# nes_controller_v1_0_v7.net
KiCad netlist of a schematic drawn in EAGLE
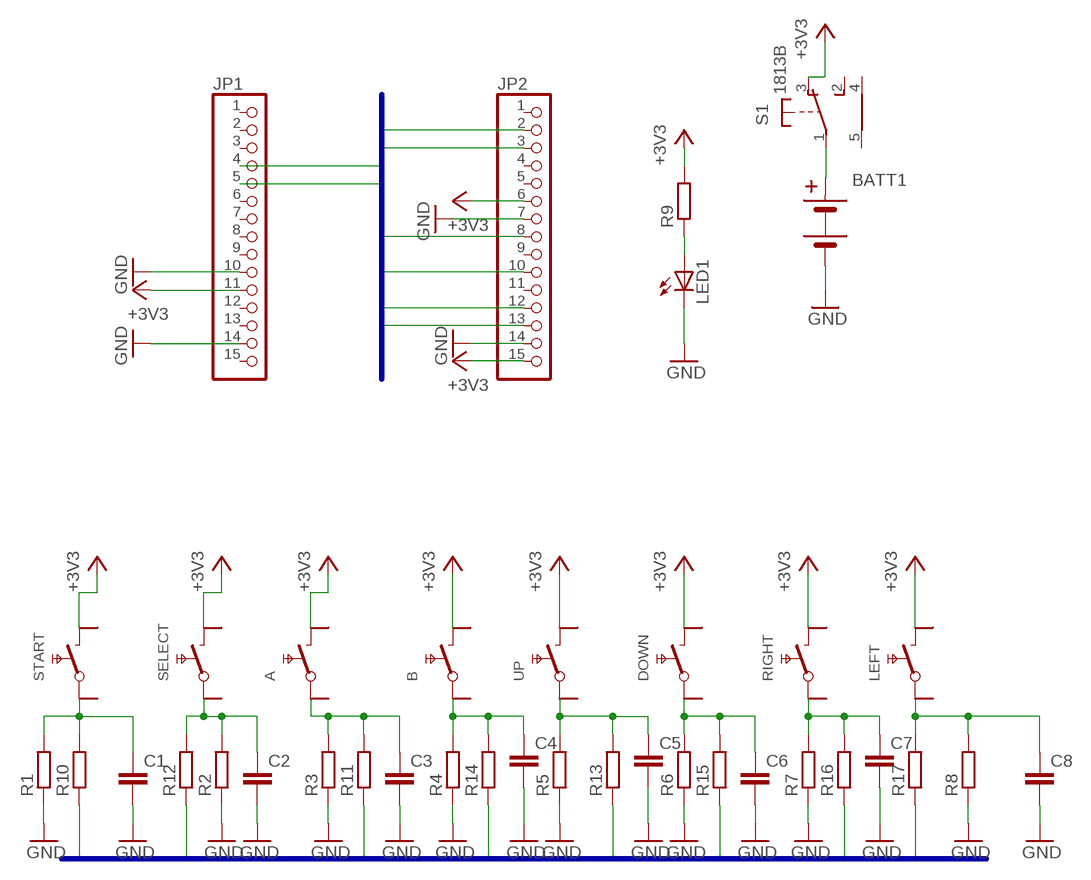
[diagram p0: schematic, sheet 1]

(export (version "E")
  (design (tool "Eeschema 10.0.6"))
  (components
    (comp (ref "A")
      (value "SMDTAST")
      (footprint "eagle-import:SMDTAST")
      (libsource (lib "eagle-import") (part "SMDTAST"))
    )
    (comp (ref "B")
      (value "SMDTAST")
      (footprint "eagle-import:SMDTAST")
      (libsource (lib "eagle-import") (part "SMDTAST"))
    )
    (comp (ref "BATT1")
      (value "BATTERIEHALTER_2X_AAA")
      (footprint "eagle-import:BATTERIEHALTER")
      (libsource (lib "eagle-import") (part "BATTERIEHALTER_2X_AAA"))
    )
    (comp (ref "C1")
      (value "C-EUC0805K")
      (footprint "eagle-import:C0805K")
      (libsource (lib "eagle-import") (part "C-EUC0805K"))
    )
    (comp (ref "C2")
      (value "C-EUC0805K")
      (footprint "eagle-import:C0805K")
      (libsource (lib "eagle-import") (part "C-EUC0805K"))
    )
    (comp (ref "C3")
      (value "C-EUC0805K")
      (footprint "eagle-import:C0805K")
      (libsource (lib "eagle-import") (part "C-EUC0805K"))
    )
    (comp (ref "C4")
      (value "C-EUC0805K")
      (footprint "eagle-import:C0805K")
      (libsource (lib "eagle-import") (part "C-EUC0805K"))
    )
    (comp (ref "C5")
      (value "C-EUC0805K")
      (footprint "eagle-import:C0805K")
      (libsource (lib "eagle-import") (part "C-EUC0805K"))
    )
    (comp (ref "C6")
      (value "C-EUC0805K")
      (footprint "eagle-import:C0805K")
      (libsource (lib "eagle-import") (part "C-EUC0805K"))
    )
    (comp (ref "C7")
      (value "C-EUC0805K")
      (footprint "eagle-import:C0805K")
      (libsource (lib "eagle-import") (part "C-EUC0805K"))
    )
    (comp (ref "C8")
      (value "C-EUC0805K")
      (footprint "eagle-import:C0805K")
      (libsource (lib "eagle-import") (part "C-EUC0805K"))
    )
    (comp (ref "DOWN")
      (value "SMDTAST")
      (footprint "eagle-import:SMDTAST")
      (libsource (lib "eagle-import") (part "SMDTAST"))
    )
    (comp (ref "JP1")
      (value "PINHD-1X15")
      (footprint "eagle-import:1X15")
      (libsource (lib "eagle-import") (part "PINHD-1X15"))
    )
    (comp (ref "JP2")
      (value "PINHD-1X15")
      (footprint "eagle-import:1X15")
      (libsource (lib "eagle-import") (part "PINHD-1X15"))
    )
    (comp (ref "LED1")
      (value "LED3MM")
      (footprint "eagle-import:LED3MM")
      (libsource (lib "eagle-import") (part "LED3MM"))
    )
    (comp (ref "LEFT")
      (value "SMDTAST")
      (footprint "eagle-import:SMDTAST")
      (libsource (lib "eagle-import") (part "SMDTAST"))
    )
    (comp (ref "R1")
      (value "R-EU_MELF0207R")
      (footprint "eagle-import:MINI_MELF-0207R")
      (libsource (lib "eagle-import") (part "R-EU_MELF0207R"))
    )
    (comp (ref "R2")
      (value "R-EU_MELF0207R")
      (footprint "eagle-import:MINI_MELF-0207R")
      (libsource (lib "eagle-import") (part "R-EU_MELF0207R"))
    )
    (comp (ref "R3")
      (value "R-EU_MELF0207R")
      (footprint "eagle-import:MINI_MELF-0207R")
      (libsource (lib "eagle-import") (part "R-EU_MELF0207R"))
    )
    (comp (ref "R4")
      (value "R-EU_MELF0207R")
      (footprint "eagle-import:MINI_MELF-0207R")
      (libsource (lib "eagle-import") (part "R-EU_MELF0207R"))
    )
    (comp (ref "R5")
      (value "R-EU_MELF0207R")
      (footprint "eagle-import:MINI_MELF-0207R")
      (libsource (lib "eagle-import") (part "R-EU_MELF0207R"))
    )
    (comp (ref "R6")
      (value "R-EU_MELF0207R")
      (footprint "eagle-import:MINI_MELF-0207R")
      (libsource (lib "eagle-import") (part "R-EU_MELF0207R"))
    )
    (comp (ref "R7")
      (value "R-EU_MELF0207R")
      (footprint "eagle-import:MINI_MELF-0207R")
      (libsource (lib "eagle-import") (part "R-EU_MELF0207R"))
    )
    (comp (ref "R8")
      (value "R-EU_MELF0207R")
      (footprint "eagle-import:MINI_MELF-0207R")
      (libsource (lib "eagle-import") (part "R-EU_MELF0207R"))
    )
    (comp (ref "R9")
      (value "R-EU_MELF0207R")
      (footprint "eagle-import:MINI_MELF-0207R")
      (libsource (lib "eagle-import") (part "R-EU_MELF0207R"))
    )
    (comp (ref "R10")
      (value "R-EU_MELF0207R")
      (footprint "eagle-import:MINI_MELF-0207R")
      (libsource (lib "eagle-import") (part "R-EU_MELF0207R"))
    )
    (comp (ref "R11")
      (value "R-EU_MELF0207R")
      (footprint "eagle-import:MINI_MELF-0207R")
      (libsource (lib "eagle-import") (part "R-EU_MELF0207R"))
    )
    (comp (ref "R12")
      (value "R-EU_MELF0207R")
      (footprint "eagle-import:MINI_MELF-0207R")
      (libsource (lib "eagle-import") (part "R-EU_MELF0207R"))
    )
    (comp (ref "R13")
      (value "R-EU_MELF0207R")
      (footprint "eagle-import:MINI_MELF-0207R")
      (libsource (lib "eagle-import") (part "R-EU_MELF0207R"))
    )
    (comp (ref "R14")
      (value "R-EU_MELF0207R")
      (footprint "eagle-import:MINI_MELF-0207R")
      (libsource (lib "eagle-import") (part "R-EU_MELF0207R"))
    )
    (comp (ref "R15")
      (value "R-EU_MELF0207R")
      (footprint "eagle-import:MINI_MELF-0207R")
      (libsource (lib "eagle-import") (part "R-EU_MELF0207R"))
    )
    (comp (ref "R16")
      (value "R-EU_MELF0207R")
      (footprint "eagle-import:MINI_MELF-0207R")
      (libsource (lib "eagle-import") (part "R-EU_MELF0207R"))
    )
    (comp (ref "R17")
      (value "R-EU_MELF0207R")
      (footprint "eagle-import:MINI_MELF-0207R")
      (libsource (lib "eagle-import") (part "R-EU_MELF0207R"))
    )
    (comp (ref "RIGHT")
      (value "SMDTAST")
      (footprint "eagle-import:SMDTAST")
      (libsource (lib "eagle-import") (part "SMDTAST"))
    )
    (comp (ref "S1")
      (value "1813B")
      (footprint "eagle-import:1813B")
      (libsource (lib "eagle-import") (part "1813B"))
    )
    (comp (ref "SELECT")
      (value "SMDTAST")
      (footprint "eagle-import:SMDTAST")
      (libsource (lib "eagle-import") (part "SMDTAST"))
    )
    (comp (ref "START")
      (value "SMDTAST")
      (footprint "eagle-import:SMDTAST")
      (libsource (lib "eagle-import") (part "SMDTAST"))
    )
    (comp (ref "UP")
      (value "SMDTAST")
      (footprint "eagle-import:SMDTAST")
      (libsource (lib "eagle-import") (part "SMDTAST"))
    )
  )
  (nets
    (net (code "1") (name "+3V3") (class "Default")
      (node (ref "A") (pin "2") (pinfunction "2_2") (pintype "bidirectional"))
      (node (ref "B") (pin "2") (pinfunction "2_2") (pintype "bidirectional"))
      (node (ref "DOWN") (pin "2") (pinfunction "2_2") (pintype "bidirectional"))
      (node (ref "JP1") (pin "11") (pinfunction "11_11") (pintype "passive"))
      (node (ref "JP2") (pin "15") (pinfunction "15_15") (pintype "passive"))
      (node (ref "JP2") (pin "6") (pinfunction "6_6") (pintype "passive"))
      (node (ref "LEFT") (pin "2") (pinfunction "2_2") (pintype "bidirectional"))
      (node (ref "R9") (pin "2") (pinfunction "2_2") (pintype "passive"))
      (node (ref "RIGHT") (pin "2") (pinfunction "2_2") (pintype "bidirectional"))
      (node (ref "S1") (pin "3") (pinfunction "O_3") (pintype "passive"))
      (node (ref "SELECT") (pin "2") (pinfunction "2_2") (pintype "bidirectional"))
      (node (ref "START") (pin "2") (pinfunction "2_2") (pintype "bidirectional"))
      (node (ref "UP") (pin "2") (pinfunction "2_2") (pintype "bidirectional"))
    )
    (net (code "2") (name "/A") (class "Default")
      (node (ref "JP1") (pin "5") (pinfunction "5_5") (pintype "passive"))
      (node (ref "R11") (pin "1") (pinfunction "1_1") (pintype "passive"))
    )
    (net (code "3") (name "/B") (class "Default")
      (node (ref "JP1") (pin "4") (pinfunction "4_4") (pintype "passive"))
      (node (ref "R14") (pin "1") (pinfunction "1_1") (pintype "passive"))
    )
    (net (code "4") (name "/DOWN") (class "Default")
      (node (ref "JP2") (pin "8") (pinfunction "8_8") (pintype "passive"))
      (node (ref "R15") (pin "1") (pinfunction "1_1") (pintype "passive"))
    )
    (net (code "5") (name "/LEFT") (class "Default")
      (node (ref "JP2") (pin "10") (pinfunction "10_10") (pintype "passive"))
      (node (ref "R17") (pin "1") (pinfunction "1_1") (pintype "passive"))
    )
    (net (code "6") (name "/RIGHT") (class "Default")
      (node (ref "JP2") (pin "13") (pinfunction "13_13") (pintype "passive"))
      (node (ref "R16") (pin "1") (pinfunction "1_1") (pintype "passive"))
    )
    (net (code "7") (name "/SELECT") (class "Default")
      (node (ref "JP2") (pin "2") (pinfunction "2_2") (pintype "passive"))
      (node (ref "R12") (pin "1") (pinfunction "1_1") (pintype "passive"))
    )
    (net (code "8") (name "/START") (class "Default")
      (node (ref "JP2") (pin "3") (pinfunction "3_3") (pintype "passive"))
      (node (ref "R10") (pin "1") (pinfunction "1_1") (pintype "passive"))
    )
    (net (code "9") (name "/UP") (class "Default")
      (node (ref "JP2") (pin "12") (pinfunction "12_12") (pintype "passive"))
      (node (ref "R13") (pin "1") (pinfunction "1_1") (pintype "passive"))
    )
    (net (code "11") (name "GND") (class "Default")
      (node (ref "BATT1") (pin "P-") (pinfunction "P-_P-") (pintype "bidirectional"))
      (node (ref "C1") (pin "2") (pinfunction "2_2") (pintype "passive"))
      (node (ref "C2") (pin "2") (pinfunction "2_2") (pintype "passive"))
      (node (ref "C3") (pin "2") (pinfunction "2_2") (pintype "passive"))
      (node (ref "C4") (pin "2") (pinfunction "2_2") (pintype "passive"))
      (node (ref "C5") (pin "2") (pinfunction "2_2") (pintype "passive"))
      (node (ref "C6") (pin "2") (pinfunction "2_2") (pintype "passive"))
      (node (ref "C7") (pin "2") (pinfunction "2_2") (pintype "passive"))
      (node (ref "C8") (pin "2") (pinfunction "2_2") (pintype "passive"))
      (node (ref "JP1") (pin "10") (pinfunction "10_10") (pintype "passive"))
      (node (ref "JP1") (pin "14") (pinfunction "14_14") (pintype "passive"))
      (node (ref "JP2") (pin "14") (pinfunction "14_14") (pintype "passive"))
      (node (ref "JP2") (pin "7") (pinfunction "7_7") (pintype "passive"))
      (node (ref "LED1") (pin "K") (pinfunction "C_K") (pintype "passive"))
      (node (ref "R1") (pin "1") (pinfunction "1_1") (pintype "passive"))
      (node (ref "R2") (pin "1") (pinfunction "1_1") (pintype "passive"))
      (node (ref "R3") (pin "1") (pinfunction "1_1") (pintype "passive"))
      (node (ref "R4") (pin "1") (pinfunction "1_1") (pintype "passive"))
      (node (ref "R5") (pin "1") (pinfunction "1_1") (pintype "passive"))
      (node (ref "R6") (pin "1") (pinfunction "1_1") (pintype "passive"))
      (node (ref "R7") (pin "1") (pinfunction "1_1") (pintype "passive"))
      (node (ref "R8") (pin "1") (pinfunction "1_1") (pintype "passive"))
    )
    (net (code "12") (name "Net-(A-Pad1)") (class "Default")
      (node (ref "A") (pin "1") (pinfunction "1_1") (pintype "bidirectional"))
      (node (ref "C3") (pin "1") (pinfunction "1_1") (pintype "passive"))
      (node (ref "R11") (pin "2") (pinfunction "2_2") (pintype "passive"))
      (node (ref "R3") (pin "2") (pinfunction "2_2") (pintype "passive"))
    )
    (net (code "13") (name "Net-(B-Pad1)") (class "Default")
      (node (ref "B") (pin "1") (pinfunction "1_1") (pintype "bidirectional"))
      (node (ref "C4") (pin "1") (pinfunction "1_1") (pintype "passive"))
      (node (ref "R14") (pin "2") (pinfunction "2_2") (pintype "passive"))
      (node (ref "R4") (pin "2") (pinfunction "2_2") (pintype "passive"))
    )
    (net (code "14") (name "Net-(C1-Pad1)") (class "Default")
      (node (ref "C1") (pin "1") (pinfunction "1_1") (pintype "passive"))
      (node (ref "R1") (pin "2") (pinfunction "2_2") (pintype "passive"))
      (node (ref "R10") (pin "2") (pinfunction "2_2") (pintype "passive"))
      (node (ref "START") (pin "1") (pinfunction "1_1") (pintype "bidirectional"))
    )
    (net (code "15") (name "Net-(C2-Pad1)") (class "Default")
      (node (ref "C2") (pin "1") (pinfunction "1_1") (pintype "passive"))
      (node (ref "R12") (pin "2") (pinfunction "2_2") (pintype "passive"))
      (node (ref "R2") (pin "2") (pinfunction "2_2") (pintype "passive"))
      (node (ref "SELECT") (pin "1") (pinfunction "1_1") (pintype "bidirectional"))
    )
    (net (code "16") (name "Net-(C5-Pad1)") (class "Default")
      (node (ref "C5") (pin "1") (pinfunction "1_1") (pintype "passive"))
      (node (ref "R13") (pin "2") (pinfunction "2_2") (pintype "passive"))
      (node (ref "R5") (pin "2") (pinfunction "2_2") (pintype "passive"))
      (node (ref "UP") (pin "1") (pinfunction "1_1") (pintype "bidirectional"))
    )
    (net (code "17") (name "Net-(C6-Pad1)") (class "Default")
      (node (ref "C6") (pin "1") (pinfunction "1_1") (pintype "passive"))
      (node (ref "DOWN") (pin "1") (pinfunction "1_1") (pintype "bidirectional"))
      (node (ref "R15") (pin "2") (pinfunction "2_2") (pintype "passive"))
      (node (ref "R6") (pin "2") (pinfunction "2_2") (pintype "passive"))
    )
    (net (code "18") (name "Net-(C7-Pad1)") (class "Default")
      (node (ref "C7") (pin "1") (pinfunction "1_1") (pintype "passive"))
      (node (ref "R16") (pin "2") (pinfunction "2_2") (pintype "passive"))
      (node (ref "R7") (pin "2") (pinfunction "2_2") (pintype "passive"))
      (node (ref "RIGHT") (pin "1") (pinfunction "1_1") (pintype "bidirectional"))
    )
    (net (code "19") (name "Net-(C8-Pad1)") (class "Default")
      (node (ref "C8") (pin "1") (pinfunction "1_1") (pintype "passive"))
      (node (ref "LEFT") (pin "1") (pinfunction "1_1") (pintype "bidirectional"))
      (node (ref "R17") (pin "2") (pinfunction "2_2") (pintype "passive"))
      (node (ref "R8") (pin "2") (pinfunction "2_2") (pintype "passive"))
    )
    (net (code "20") (name "Net-(LED1-PadA)") (class "Default")
      (node (ref "LED1") (pin "A") (pinfunction "A_A") (pintype "passive"))
      (node (ref "R9") (pin "1") (pinfunction "1_1") (pintype "passive"))
    )
    (net (code "21") (name "Net-(S1-W)") (class "Default")
      (node (ref "BATT1") (pin "P+") (pinfunction "P+_P+") (pintype "bidirectional"))
      (node (ref "S1") (pin "1") (pinfunction "W_1") (pintype "passive"))
    )
    (net (code "22") (name "unconnected-(A-Pad11)") (class "Default")
      (node (ref "A") (pin "11") (pinfunction "11_11") (pintype "bidirectional"))
    )
    (net (code "23") (name "unconnected-(A-Pad22)") (class "Default")
      (node (ref "A") (pin "22") (pinfunction "22_22") (pintype "bidirectional"))
    )
    (net (code "24") (name "unconnected-(B-Pad11)") (class "Default")
      (node (ref "B") (pin "11") (pinfunction "11_11") (pintype "bidirectional"))
    )
    (net (code "25") (name "unconnected-(B-Pad22)") (class "Default")
      (node (ref "B") (pin "22") (pinfunction "22_22") (pintype "bidirectional"))
    )
    (net (code "26") (name "unconnected-(DOWN-Pad11)") (class "Default")
      (node (ref "DOWN") (pin "11") (pinfunction "11_11") (pintype "bidirectional"))
    )
    (net (code "27") (name "unconnected-(DOWN-Pad22)") (class "Default")
      (node (ref "DOWN") (pin "22") (pinfunction "22_22") (pintype "bidirectional"))
    )
    (net (code "28") (name "unconnected-(JP1-Pad1)") (class "Default")
      (node (ref "JP1") (pin "1") (pinfunction "1_1") (pintype "passive"))
    )
    (net (code "29") (name "unconnected-(JP1-Pad2)") (class "Default")
      (node (ref "JP1") (pin "2") (pinfunction "2_2") (pintype "passive"))
    )
    (net (code "30") (name "unconnected-(JP1-Pad3)") (class "Default")
      (node (ref "JP1") (pin "3") (pinfunction "3_3") (pintype "passive"))
    )
    (net (code "31") (name "unconnected-(JP1-Pad6)") (class "Default")
      (node (ref "JP1") (pin "6") (pinfunction "6_6") (pintype "passive"))
    )
    (net (code "32") (name "unconnected-(JP1-Pad7)") (class "Default")
      (node (ref "JP1") (pin "7") (pinfunction "7_7") (pintype "passive"))
    )
    (net (code "33") (name "unconnected-(JP1-Pad8)") (class "Default")
      (node (ref "JP1") (pin "8") (pinfunction "8_8") (pintype "passive"))
    )
    (net (code "34") (name "unconnected-(JP1-Pad9)") (class "Default")
      (node (ref "JP1") (pin "9") (pinfunction "9_9") (pintype "passive"))
    )
    (net (code "35") (name "unconnected-(JP1-Pad12)") (class "Default")
      (node (ref "JP1") (pin "12") (pinfunction "12_12") (pintype "passive"))
    )
    (net (code "36") (name "unconnected-(JP1-Pad13)") (class "Default")
      (node (ref "JP1") (pin "13") (pinfunction "13_13") (pintype "passive"))
    )
    (net (code "37") (name "unconnected-(JP1-Pad15)") (class "Default")
      (node (ref "JP1") (pin "15") (pinfunction "15_15") (pintype "passive"))
    )
    (net (code "38") (name "unconnected-(JP2-Pad1)") (class "Default")
      (node (ref "JP2") (pin "1") (pinfunction "1_1") (pintype "passive"))
    )
    (net (code "39") (name "unconnected-(JP2-Pad4)") (class "Default")
      (node (ref "JP2") (pin "4") (pinfunction "4_4") (pintype "passive"))
    )
    (net (code "40") (name "unconnected-(JP2-Pad5)") (class "Default")
      (node (ref "JP2") (pin "5") (pinfunction "5_5") (pintype "passive"))
    )
    (net (code "41") (name "unconnected-(JP2-Pad9)") (class "Default")
      (node (ref "JP2") (pin "9") (pinfunction "9_9") (pintype "passive"))
    )
    (net (code "42") (name "unconnected-(JP2-Pad11)") (class "Default")
      (node (ref "JP2") (pin "11") (pinfunction "11_11") (pintype "passive"))
    )
    (net (code "43") (name "unconnected-(LEFT-Pad11)") (class "Default")
      (node (ref "LEFT") (pin "11") (pinfunction "11_11") (pintype "bidirectional"))
    )
    (net (code "44") (name "unconnected-(LEFT-Pad22)") (class "Default")
      (node (ref "LEFT") (pin "22") (pinfunction "22_22") (pintype "bidirectional"))
    )
    (net (code "45") (name "unconnected-(RIGHT-Pad11)") (class "Default")
      (node (ref "RIGHT") (pin "11") (pinfunction "11_11") (pintype "bidirectional"))
    )
    (net (code "46") (name "unconnected-(RIGHT-Pad22)") (class "Default")
      (node (ref "RIGHT") (pin "22") (pinfunction "22_22") (pintype "bidirectional"))
    )
    (net (code "47") (name "unconnected-(S1-S-Pad2)") (class "Default")
      (node (ref "S1") (pin "2") (pinfunction "S_2") (pintype "passive"))
    )
    (net (code "48") (name "unconnected-(S1-SH1-Pad4)") (class "Default")
      (node (ref "S1") (pin "4") (pinfunction "SH1_4") (pintype "passive"))
    )
    (net (code "49") (name "unconnected-(S1-SH2-Pad5)") (class "Default")
      (node (ref "S1") (pin "5") (pinfunction "SH2_5") (pintype "passive"))
    )
    (net (code "50") (name "unconnected-(SELECT-Pad11)") (class "Default")
      (node (ref "SELECT") (pin "11") (pinfunction "11_11") (pintype "bidirectional"))
    )
    (net (code "51") (name "unconnected-(SELECT-Pad22)") (class "Default")
      (node (ref "SELECT") (pin "22") (pinfunction "22_22") (pintype "bidirectional"))
    )
    (net (code "52") (name "unconnected-(START-Pad11)") (class "Default")
      (node (ref "START") (pin "11") (pinfunction "11_11") (pintype "bidirectional"))
    )
    (net (code "53") (name "unconnected-(START-Pad22)") (class "Default")
      (node (ref "START") (pin "22") (pinfunction "22_22") (pintype "bidirectional"))
    )
    (net (code "54") (name "unconnected-(UP-Pad11)") (class "Default")
      (node (ref "UP") (pin "11") (pinfunction "11_11") (pintype "bidirectional"))
    )
    (net (code "55") (name "unconnected-(UP-Pad22)") (class "Default")
      (node (ref "UP") (pin "22") (pinfunction "22_22") (pintype "bidirectional"))
    )
  )
)
